# 32_LED.net
KiCad netlist of a schematic drawn in Altium Designer
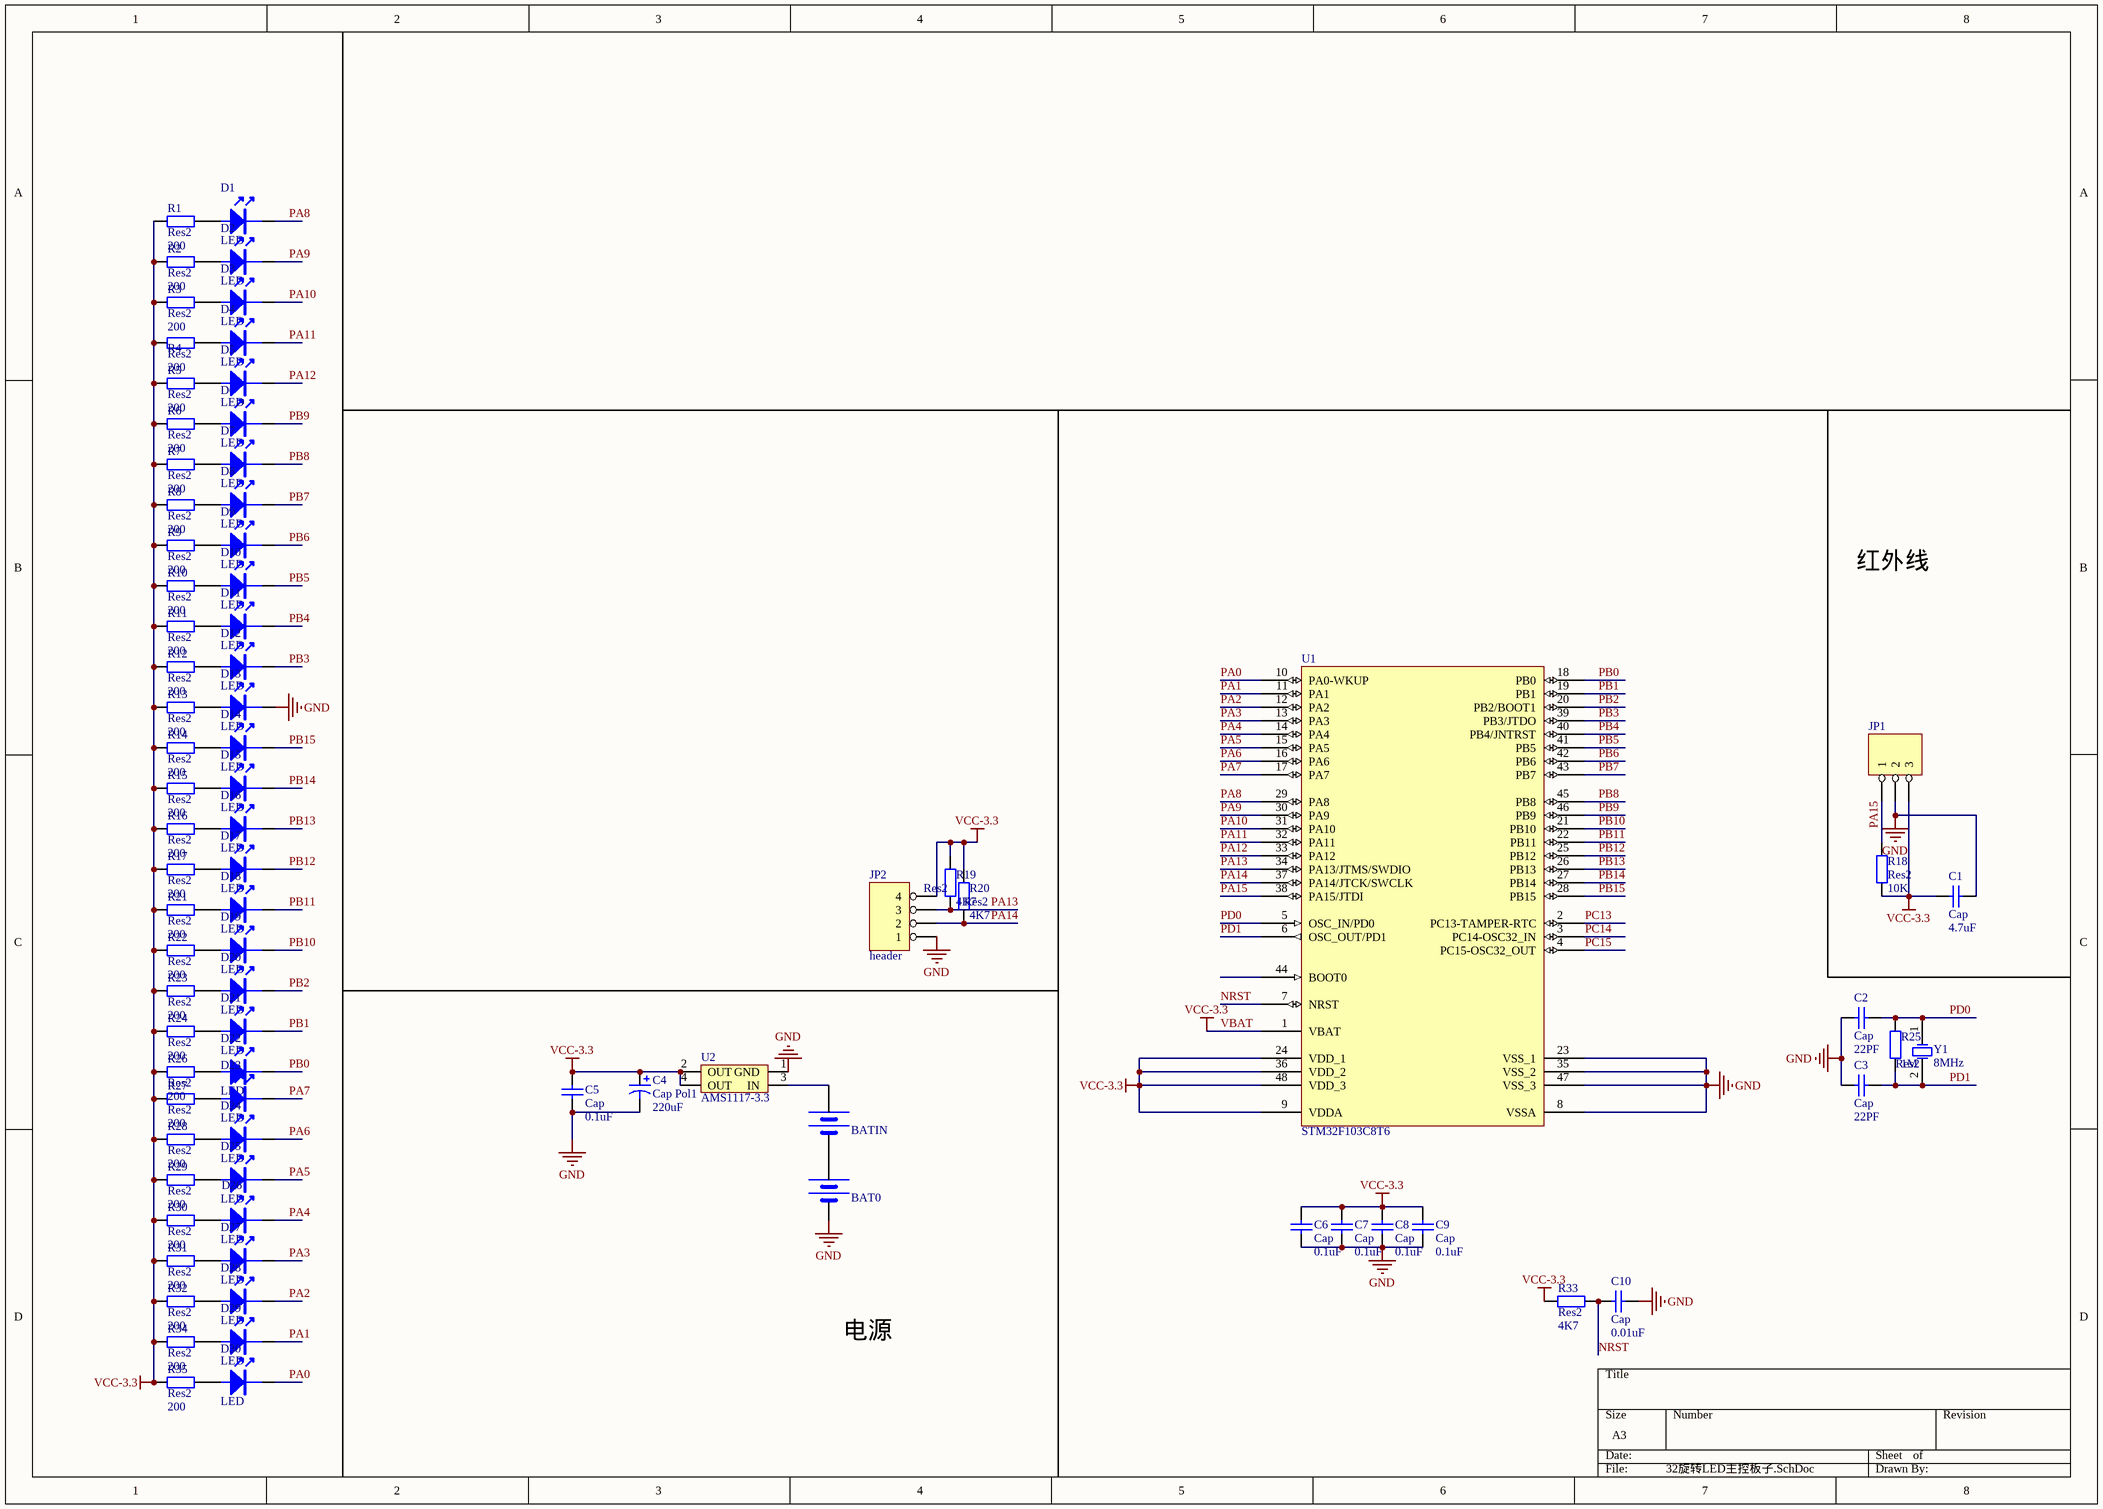
[diagram p0: 32旋转LED主控板子.SchDoc]

(export (version "E")
  (design (tool "Eeschema 10.0.6"))
  (components
    (comp (ref "BAT0")
      (value "BATT")
      (footprint "BATM")
      (libsource (lib "Explorer STM32F407封装库") (part "BAT"))
    )
    (comp (ref "BATIN")
      (value "BATT")
      (footprint "BATM")
      (libsource (lib "Explorer STM32F407封装库") (part "BAT"))
    )
    (comp (ref "C1")
      (value "Cap")
      (footprint "0805_C")
      (description "Capacitor")
      (fields (field (name "ALTIUM_VALUE") "4.7uF") (field (name "PUBLISHER") "Altium Limited"))
      (libsource (lib "Miscellaneous Devices") (part "Cap"))
    )
    (comp (ref "C2")
      (value "Cap")
      (footprint "0805_C")
      (description "Capacitor")
      (fields (field (name "ALTIUM_VALUE") "22PF") (field (name "PUBLISHER") "Altium Limited"))
      (libsource (lib "Miscellaneous Devices") (part "Cap"))
    )
    (comp (ref "C3")
      (value "Cap")
      (footprint "0805_C")
      (description "Capacitor")
      (fields (field (name "ALTIUM_VALUE") "22PF") (field (name "PUBLISHER") "Altium Limited"))
      (libsource (lib "Miscellaneous Devices") (part "Cap"))
    )
    (comp (ref "C4")
      (value "Cap Pol1")
      (footprint "10UF")
      (description "Polarized Capacitor (Radial)")
      (fields (field (name "ALTIUM_VALUE") "220uF") (field (name "PUBLISHER") "Altium Limited"))
      (libsource (lib "Miscellaneous Devices") (part "Cap Pol1"))
    )
    (comp (ref "C5")
      (value "Cap")
      (footprint "0805_C")
      (description "Capacitor")
      (fields (field (name "ALTIUM_VALUE") "0.1uF") (field (name "PUBLISHER") "Altium Limited"))
      (libsource (lib "Miscellaneous Devices") (part "Cap"))
    )
    (comp (ref "C6")
      (value "Cap")
      (footprint "0805_C")
      (description "Capacitor")
      (fields (field (name "ALTIUM_VALUE") "0.1uF") (field (name "PUBLISHER") "Altium Limited"))
      (libsource (lib "Miscellaneous Devices") (part "Cap"))
    )
    (comp (ref "C7")
      (value "Cap")
      (footprint "0805_C")
      (description "Capacitor")
      (fields (field (name "ALTIUM_VALUE") "0.1uF") (field (name "PUBLISHER") "Altium Limited"))
      (libsource (lib "Miscellaneous Devices") (part "Cap"))
    )
    (comp (ref "C8")
      (value "Cap")
      (footprint "0805_C")
      (description "Capacitor")
      (fields (field (name "ALTIUM_VALUE") "0.1uF") (field (name "PUBLISHER") "Altium Limited"))
      (libsource (lib "Miscellaneous Devices") (part "Cap"))
    )
    (comp (ref "C9")
      (value "Cap")
      (footprint "0805_C")
      (description "Capacitor")
      (fields (field (name "ALTIUM_VALUE") "0.1uF") (field (name "PUBLISHER") "Altium Limited"))
      (libsource (lib "Miscellaneous Devices") (part "Cap"))
    )
    (comp (ref "C10")
      (value "Cap")
      (footprint "0805_C")
      (description "Capacitor")
      (fields (field (name "ALTIUM_VALUE") "0.01uF") (field (name "PUBLISHER") "Altium Limited"))
      (libsource (lib "Miscellaneous Devices") (part "Cap"))
    )
    (comp (ref "D1")
      (value "LED")
      (footprint "0805_LED")
      (description "LED 发光二极管")
      (libsource (lib "My Footprint") (part "LED"))
    )
    (comp (ref "D2")
      (value "LED")
      (footprint "0805_LED")
      (description "LED 发光二极管")
      (libsource (lib "My Footprint") (part "LED"))
    )
    (comp (ref "D3")
      (value "LED")
      (footprint "0805_LED")
      (description "LED 发光二极管")
      (libsource (lib "My Footprint") (part "LED"))
    )
    (comp (ref "D4")
      (value "LED")
      (footprint "0805_LED")
      (description "LED 发光二极管")
      (libsource (lib "My Footprint") (part "LED"))
    )
    (comp (ref "D5")
      (value "LED")
      (footprint "0805_LED")
      (description "LED 发光二极管")
      (libsource (lib "My Footprint") (part "LED"))
    )
    (comp (ref "D6")
      (value "LED")
      (footprint "0805_LED")
      (description "LED 发光二极管")
      (libsource (lib "My Footprint") (part "LED"))
    )
    (comp (ref "D7")
      (value "LED")
      (footprint "0805_LED")
      (description "LED 发光二极管")
      (libsource (lib "My Footprint") (part "LED"))
    )
    (comp (ref "D8")
      (value "LED")
      (footprint "0805_LED")
      (description "LED 发光二极管")
      (libsource (lib "My Footprint") (part "LED"))
    )
    (comp (ref "D9")
      (value "LED")
      (footprint "0805_LED")
      (description "LED 发光二极管")
      (libsource (lib "My Footprint") (part "LED"))
    )
    (comp (ref "D10")
      (value "LED")
      (footprint "0805_LED")
      (description "LED 发光二极管")
      (libsource (lib "My Footprint") (part "LED"))
    )
    (comp (ref "D11")
      (value "LED")
      (footprint "0805_LED")
      (description "LED 发光二极管")
      (libsource (lib "My Footprint") (part "LED"))
    )
    (comp (ref "D12")
      (value "LED")
      (footprint "0805_LED")
      (description "LED 发光二极管")
      (libsource (lib "My Footprint") (part "LED"))
    )
    (comp (ref "D13")
      (value "LED")
      (footprint "0805_LED")
      (description "LED 发光二极管")
      (libsource (lib "My Footprint") (part "LED"))
    )
    (comp (ref "D14")
      (value "LED")
      (footprint "0805_LED")
      (description "LED 发光二极管")
      (libsource (lib "My Footprint") (part "LED"))
    )
    (comp (ref "D15")
      (value "LED")
      (footprint "0805_LED")
      (description "LED 发光二极管")
      (libsource (lib "My Footprint") (part "LED"))
    )
    (comp (ref "D16")
      (value "LED")
      (footprint "0805_LED")
      (description "LED 发光二极管")
      (libsource (lib "My Footprint") (part "LED"))
    )
    (comp (ref "D17")
      (value "LED")
      (footprint "0805_LED")
      (description "LED 发光二极管")
      (libsource (lib "My Footprint") (part "LED"))
    )
    (comp (ref "D18")
      (value "LED")
      (footprint "0805_LED")
      (description "LED 发光二极管")
      (libsource (lib "My Footprint") (part "LED"))
    )
    (comp (ref "D19")
      (value "LED")
      (footprint "0805_LED")
      (description "LED 发光二极管")
      (libsource (lib "My Footprint") (part "LED"))
    )
    (comp (ref "D20")
      (value "LED")
      (footprint "0805_LED")
      (description "LED 发光二极管")
      (libsource (lib "My Footprint") (part "LED"))
    )
    (comp (ref "D21")
      (value "LED")
      (footprint "0805_LED")
      (description "LED 发光二极管")
      (libsource (lib "My Footprint") (part "LED"))
    )
    (comp (ref "D22")
      (value "LED")
      (footprint "0805_LED")
      (description "LED 发光二极管")
      (libsource (lib "My Footprint") (part "LED"))
    )
    (comp (ref "D23")
      (value "LED")
      (footprint "0805_LED")
      (description "LED 发光二极管")
      (libsource (lib "My Footprint") (part "LED"))
    )
    (comp (ref "D24")
      (value "LED")
      (footprint "0805_LED")
      (description "LED 发光二极管")
      (libsource (lib "My Footprint") (part "LED"))
    )
    (comp (ref "D25")
      (value "LED")
      (footprint "0805_LED")
      (description "LED 发光二极管")
      (libsource (lib "My Footprint") (part "LED"))
    )
    (comp (ref "D26")
      (value "LED")
      (footprint "0805_LED")
      (description "LED 发光二极管")
      (libsource (lib "My Footprint") (part "LED"))
    )
    (comp (ref "D27")
      (value "LED")
      (footprint "0805_LED")
      (description "LED 发光二极管")
      (libsource (lib "My Footprint") (part "LED"))
    )
    (comp (ref "D28")
      (value "LED")
      (footprint "0805_LED")
      (description "LED 发光二极管")
      (libsource (lib "My Footprint") (part "LED"))
    )
    (comp (ref "D29")
      (value "LED")
      (footprint "0805_LED")
      (description "LED 发光二极管")
      (libsource (lib "My Footprint") (part "LED"))
    )
    (comp (ref "D30")
      (value "LED")
      (footprint "0805_LED")
      (description "LED 发光二极管")
      (libsource (lib "My Footprint") (part "LED"))
    )
    (comp (ref "JP1")
      (value "header")
      (footprint "header3")
      (libsource (lib "My Footprint") (part "HEADER 3"))
    )
    (comp (ref "JP2")
      (value "header")
      (footprint "header4")
      (libsource (lib "My Footprint") (part "HEADER 4"))
    )
    (comp (ref "R1")
      (value "Res2")
      (footprint "0805_R")
      (description "Resistor")
      (fields (field (name "ALTIUM_VALUE") "200") (field (name "PUBLISHER") "Altium Limited"))
      (libsource (lib "Miscellaneous Devices") (part "Res2"))
    )
    (comp (ref "R2")
      (value "Res2")
      (footprint "0805_R")
      (description "Resistor")
      (fields (field (name "ALTIUM_VALUE") "200") (field (name "PUBLISHER") "Altium Limited"))
      (libsource (lib "Miscellaneous Devices") (part "Res2"))
    )
    (comp (ref "R3")
      (value "Res2")
      (footprint "0805_R")
      (description "Resistor")
      (fields (field (name "ALTIUM_VALUE") "200") (field (name "PUBLISHER") "Altium Limited"))
      (libsource (lib "Miscellaneous Devices") (part "Res2"))
    )
    (comp (ref "R4")
      (value "Res2")
      (footprint "0805_R")
      (description "Resistor")
      (fields (field (name "ALTIUM_VALUE") "200") (field (name "PUBLISHER") "Altium Limited"))
      (libsource (lib "Miscellaneous Devices") (part "Res2"))
    )
    (comp (ref "R5")
      (value "Res2")
      (footprint "0805_R")
      (description "Resistor")
      (fields (field (name "ALTIUM_VALUE") "200") (field (name "PUBLISHER") "Altium Limited"))
      (libsource (lib "Miscellaneous Devices") (part "Res2"))
    )
    (comp (ref "R6")
      (value "Res2")
      (footprint "0805_R")
      (description "Resistor")
      (fields (field (name "ALTIUM_VALUE") "200") (field (name "PUBLISHER") "Altium Limited"))
      (libsource (lib "Miscellaneous Devices") (part "Res2"))
    )
    (comp (ref "R7")
      (value "Res2")
      (footprint "0805_R")
      (description "Resistor")
      (fields (field (name "ALTIUM_VALUE") "200") (field (name "PUBLISHER") "Altium Limited"))
      (libsource (lib "Miscellaneous Devices") (part "Res2"))
    )
    (comp (ref "R8")
      (value "Res2")
      (footprint "0805_R")
      (description "Resistor")
      (fields (field (name "ALTIUM_VALUE") "200") (field (name "PUBLISHER") "Altium Limited"))
      (libsource (lib "Miscellaneous Devices") (part "Res2"))
    )
    (comp (ref "R9")
      (value "Res2")
      (footprint "0805_R")
      (description "Resistor")
      (fields (field (name "ALTIUM_VALUE") "200") (field (name "PUBLISHER") "Altium Limited"))
      (libsource (lib "Miscellaneous Devices") (part "Res2"))
    )
    (comp (ref "R10")
      (value "Res2")
      (footprint "0805_R")
      (description "Resistor")
      (fields (field (name "ALTIUM_VALUE") "200") (field (name "PUBLISHER") "Altium Limited"))
      (libsource (lib "Miscellaneous Devices") (part "Res2"))
    )
    (comp (ref "R11")
      (value "Res2")
      (footprint "0805_R")
      (description "Resistor")
      (fields (field (name "ALTIUM_VALUE") "200") (field (name "PUBLISHER") "Altium Limited"))
      (libsource (lib "Miscellaneous Devices") (part "Res2"))
    )
    (comp (ref "R12")
      (value "Res2")
      (footprint "0805_R")
      (description "Resistor")
      (fields (field (name "ALTIUM_VALUE") "200") (field (name "PUBLISHER") "Altium Limited"))
      (libsource (lib "Miscellaneous Devices") (part "Res2"))
    )
    (comp (ref "R13")
      (value "Res2")
      (footprint "0805_R")
      (description "Resistor")
      (fields (field (name "ALTIUM_VALUE") "200") (field (name "PUBLISHER") "Altium Limited"))
      (libsource (lib "Miscellaneous Devices") (part "Res2"))
    )
    (comp (ref "R14")
      (value "Res2")
      (footprint "0805_R")
      (description "Resistor")
      (fields (field (name "ALTIUM_VALUE") "200") (field (name "PUBLISHER") "Altium Limited"))
      (libsource (lib "Miscellaneous Devices") (part "Res2"))
    )
    (comp (ref "R15")
      (value "Res2")
      (footprint "0805_R")
      (description "Resistor")
      (fields (field (name "ALTIUM_VALUE") "200") (field (name "PUBLISHER") "Altium Limited"))
      (libsource (lib "Miscellaneous Devices") (part "Res2"))
    )
    (comp (ref "R16")
      (value "Res2")
      (footprint "0805_R")
      (description "Resistor")
      (fields (field (name "ALTIUM_VALUE") "200") (field (name "PUBLISHER") "Altium Limited"))
      (libsource (lib "Miscellaneous Devices") (part "Res2"))
    )
    (comp (ref "R17")
      (value "Res2")
      (footprint "0805_R")
      (description "Resistor")
      (fields (field (name "ALTIUM_VALUE") "200") (field (name "PUBLISHER") "Altium Limited"))
      (libsource (lib "Miscellaneous Devices") (part "Res2"))
    )
    (comp (ref "R18")
      (value "Res2")
      (footprint "0805_R")
      (description "Resistor")
      (fields (field (name "ALTIUM_VALUE") "10K") (field (name "PUBLISHER") "Altium Limited"))
      (libsource (lib "") (part "Res2_1"))
    )
    (comp (ref "R19")
      (value "Res2")
      (footprint "0805_R")
      (description "Resistor")
      (fields (field (name "ALTIUM_VALUE") "4K7") (field (name "PUBLISHER") "Altium Limited"))
      (libsource (lib "") (part "Res2_1"))
    )
    (comp (ref "R20")
      (value "Res2")
      (footprint "0805_R")
      (description "Resistor")
      (fields (field (name "ALTIUM_VALUE") "4K7") (field (name "PUBLISHER") "Altium Limited"))
      (libsource (lib "") (part "Res2_1"))
    )
    (comp (ref "R21")
      (value "Res2")
      (footprint "0805_R")
      (description "Resistor")
      (fields (field (name "ALTIUM_VALUE") "200") (field (name "PUBLISHER") "Altium Limited"))
      (libsource (lib "Miscellaneous Devices") (part "Res2"))
    )
    (comp (ref "R22")
      (value "Res2")
      (footprint "0805_R")
      (description "Resistor")
      (fields (field (name "ALTIUM_VALUE") "200") (field (name "PUBLISHER") "Altium Limited"))
      (libsource (lib "Miscellaneous Devices") (part "Res2"))
    )
    (comp (ref "R23")
      (value "Res2")
      (footprint "0805_R")
      (description "Resistor")
      (fields (field (name "ALTIUM_VALUE") "200") (field (name "PUBLISHER") "Altium Limited"))
      (libsource (lib "Miscellaneous Devices") (part "Res2"))
    )
    (comp (ref "R24")
      (value "Res2")
      (footprint "0805_R")
      (description "Resistor")
      (fields (field (name "ALTIUM_VALUE") "200") (field (name "PUBLISHER") "Altium Limited"))
      (libsource (lib "Miscellaneous Devices") (part "Res2"))
    )
    (comp (ref "R25")
      (value "Res2")
      (footprint "0805_R")
      (description "Resistor")
      (fields (field (name "ALTIUM_VALUE") "1M") (field (name "PUBLISHER") "Altium Limited"))
      (libsource (lib "") (part "Res2_1"))
    )
    (comp (ref "R26")
      (value "Res2")
      (footprint "0805_R")
      (description "Resistor")
      (fields (field (name "ALTIUM_VALUE") "200") (field (name "PUBLISHER") "Altium Limited"))
      (libsource (lib "Miscellaneous Devices") (part "Res2"))
    )
    (comp (ref "R27")
      (value "Res2")
      (footprint "0805_R")
      (description "Resistor")
      (fields (field (name "ALTIUM_VALUE") "200") (field (name "PUBLISHER") "Altium Limited"))
      (libsource (lib "Miscellaneous Devices") (part "Res2"))
    )
    (comp (ref "R28")
      (value "Res2")
      (footprint "0805_R")
      (description "Resistor")
      (fields (field (name "ALTIUM_VALUE") "200") (field (name "PUBLISHER") "Altium Limited"))
      (libsource (lib "Miscellaneous Devices") (part "Res2"))
    )
    (comp (ref "R29")
      (value "Res2")
      (footprint "0805_R")
      (description "Resistor")
      (fields (field (name "ALTIUM_VALUE") "200") (field (name "PUBLISHER") "Altium Limited"))
      (libsource (lib "Miscellaneous Devices") (part "Res2"))
    )
    (comp (ref "R30")
      (value "Res2")
      (footprint "0805_R")
      (description "Resistor")
      (fields (field (name "ALTIUM_VALUE") "200") (field (name "PUBLISHER") "Altium Limited"))
      (libsource (lib "Miscellaneous Devices") (part "Res2"))
    )
    (comp (ref "R31")
      (value "Res2")
      (footprint "0805_R")
      (description "Resistor")
      (fields (field (name "ALTIUM_VALUE") "200") (field (name "PUBLISHER") "Altium Limited"))
      (libsource (lib "Miscellaneous Devices") (part "Res2"))
    )
    (comp (ref "R32")
      (value "Res2")
      (footprint "0805_R")
      (description "Resistor")
      (fields (field (name "ALTIUM_VALUE") "200") (field (name "PUBLISHER") "Altium Limited"))
      (libsource (lib "Miscellaneous Devices") (part "Res2"))
    )
    (comp (ref "R33")
      (value "Res2")
      (footprint "0805_R")
      (description "Resistor")
      (fields (field (name "ALTIUM_VALUE") "4K7") (field (name "PUBLISHER") "Altium Limited"))
      (libsource (lib "") (part "Res2_2"))
    )
    (comp (ref "R34")
      (value "Res2")
      (footprint "0805_R")
      (description "Resistor")
      (fields (field (name "ALTIUM_VALUE") "200") (field (name "PUBLISHER") "Altium Limited"))
      (libsource (lib "Miscellaneous Devices") (part "Res2"))
    )
    (comp (ref "R35")
      (value "Res2")
      (footprint "0805_R")
      (description "Resistor")
      (fields (field (name "ALTIUM_VALUE") "200") (field (name "PUBLISHER") "Altium Limited"))
      (libsource (lib "Miscellaneous Devices") (part "Res2"))
    )
    (comp (ref "U1")
      (value "STM32F103C8T6")
      (footprint "LQFP48")
      (description "STM32 ARM-based 32-bit MCU with 64 Kbytes Flash, 48-pin LQFP, Industrial Temperature")
      (fields (field (name "PUBLISHER") "Altium Limited"))
      (libsource (lib "My Footprint") (part "STM32F103C8T6"))
    )
    (comp (ref "U2")
      (value "AMS1117-3.3")
      (footprint "AMS1117")
      (libsource (lib "Explorer STM32F407封装库") (part "AMS1117"))
    )
    (comp (ref "Y1")
      (value "8MHz")
      (footprint "XTAL_2")
      (description "Crystal Oscillator")
      (fields (field (name "PUBLISHER") "Altium Limited"))
      (libsource (lib "Explorer STM32F407封装库") (part "XTAL"))
    )
  )
  (nets
    (net (code "1") (name "/NRST") (class "Default")
      (node (ref "C10") (pin "1") (pinfunction "1_1") (pintype "passive"))
      (node (ref "R33") (pin "2") (pinfunction "2_2") (pintype "passive"))
      (node (ref "U1") (pin "7") (pinfunction "NRST_7") (pintype "bidirectional"))
    )
    (net (code "2") (name "/PA0") (class "Default")
      (node (ref "D30") (pin "2") (pinfunction "K_2") (pintype "passive"))
      (node (ref "U1") (pin "10") (pinfunction "PA0-WKUP_10") (pintype "bidirectional"))
    )
    (net (code "3") (name "/PA1") (class "Default")
      (node (ref "D29") (pin "2") (pinfunction "K_2") (pintype "passive"))
      (node (ref "U1") (pin "11") (pinfunction "PA1_11") (pintype "bidirectional"))
    )
    (net (code "4") (name "/PA2") (class "Default")
      (node (ref "D28") (pin "2") (pinfunction "K_2") (pintype "passive"))
      (node (ref "U1") (pin "12") (pinfunction "PA2_12") (pintype "bidirectional"))
    )
    (net (code "5") (name "/PA3") (class "Default")
      (node (ref "D27") (pin "2") (pinfunction "K_2") (pintype "passive"))
      (node (ref "U1") (pin "13") (pinfunction "PA3_13") (pintype "bidirectional"))
    )
    (net (code "6") (name "/PA4") (class "Default")
      (node (ref "D26") (pin "2") (pinfunction "K_2") (pintype "passive"))
      (node (ref "U1") (pin "14") (pinfunction "PA4_14") (pintype "bidirectional"))
    )
    (net (code "7") (name "/PA5") (class "Default")
      (node (ref "D25") (pin "2") (pinfunction "K_2") (pintype "passive"))
      (node (ref "U1") (pin "15") (pinfunction "PA5_15") (pintype "bidirectional"))
    )
    (net (code "8") (name "/PA6") (class "Default")
      (node (ref "D24") (pin "2") (pinfunction "K_2") (pintype "passive"))
      (node (ref "U1") (pin "16") (pinfunction "PA6_16") (pintype "bidirectional"))
    )
    (net (code "9") (name "/PA7") (class "Default")
      (node (ref "D23") (pin "2") (pinfunction "K_2") (pintype "passive"))
      (node (ref "U1") (pin "17") (pinfunction "PA7_17") (pintype "bidirectional"))
    )
    (net (code "10") (name "/PA8") (class "Default")
      (node (ref "D1") (pin "2") (pinfunction "K_2") (pintype "passive"))
      (node (ref "U1") (pin "29") (pinfunction "PA8_29") (pintype "bidirectional"))
    )
    (net (code "11") (name "/PA9") (class "Default")
      (node (ref "D2") (pin "2") (pinfunction "K_2") (pintype "passive"))
      (node (ref "U1") (pin "30") (pinfunction "PA9_30") (pintype "bidirectional"))
    )
    (net (code "12") (name "/PA10") (class "Default")
      (node (ref "D3") (pin "2") (pinfunction "K_2") (pintype "passive"))
      (node (ref "U1") (pin "31") (pinfunction "PA10_31") (pintype "bidirectional"))
    )
    (net (code "13") (name "/PA11") (class "Default")
      (node (ref "D4") (pin "2") (pinfunction "K_2") (pintype "passive"))
      (node (ref "U1") (pin "32") (pinfunction "PA11_32") (pintype "bidirectional"))
    )
    (net (code "14") (name "/PA12") (class "Default")
      (node (ref "D5") (pin "2") (pinfunction "K_2") (pintype "passive"))
      (node (ref "U1") (pin "33") (pinfunction "PA12_33") (pintype "bidirectional"))
    )
    (net (code "15") (name "/PA13") (class "Default")
      (node (ref "JP2") (pin "3") (pinfunction "3_3") (pintype "passive"))
      (node (ref "R19") (pin "1") (pinfunction "1_1") (pintype "passive"))
      (node (ref "U1") (pin "34") (pinfunction "PA13/JTMS/SWDIO_34") (pintype "bidirectional"))
    )
    (net (code "16") (name "/PA14") (class "Default")
      (node (ref "JP2") (pin "2") (pinfunction "2_2") (pintype "passive"))
      (node (ref "R20") (pin "1") (pinfunction "1_1") (pintype "passive"))
      (node (ref "U1") (pin "37") (pinfunction "PA14/JTCK/SWCLK_37") (pintype "bidirectional"))
    )
    (net (code "17") (name "/PA15") (class "Default")
      (node (ref "JP1") (pin "1") (pinfunction "1_1") (pintype "passive"))
      (node (ref "R18") (pin "2") (pinfunction "2_2") (pintype "passive"))
      (node (ref "U1") (pin "38") (pinfunction "PA15/JTDI_38") (pintype "bidirectional"))
    )
    (net (code "18") (name "/PB0") (class "Default")
      (node (ref "D22") (pin "2") (pinfunction "K_2") (pintype "passive"))
      (node (ref "U1") (pin "18") (pinfunction "PB0_18") (pintype "bidirectional"))
    )
    (net (code "19") (name "/PB1") (class "Default")
      (node (ref "D21") (pin "2") (pinfunction "K_2") (pintype "passive"))
      (node (ref "U1") (pin "19") (pinfunction "PB1_19") (pintype "bidirectional"))
    )
    (net (code "20") (name "/PB2") (class "Default")
      (node (ref "D20") (pin "2") (pinfunction "K_2") (pintype "passive"))
      (node (ref "U1") (pin "20") (pinfunction "PB2/BOOT1_20") (pintype "bidirectional"))
    )
    (net (code "21") (name "/PB3") (class "Default")
      (node (ref "D12") (pin "2") (pinfunction "K_2") (pintype "passive"))
      (node (ref "U1") (pin "39") (pinfunction "PB3/JTDO_39") (pintype "bidirectional"))
    )
    (net (code "22") (name "/PB4") (class "Default")
      (node (ref "D11") (pin "2") (pinfunction "K_2") (pintype "passive"))
      (node (ref "U1") (pin "40") (pinfunction "PB4/JNTRST_40") (pintype "bidirectional"))
    )
    (net (code "23") (name "/PB5") (class "Default")
      (node (ref "D10") (pin "2") (pinfunction "K_2") (pintype "passive"))
      (node (ref "U1") (pin "41") (pinfunction "PB5_41") (pintype "bidirectional"))
    )
    (net (code "24") (name "/PB6") (class "Default")
      (node (ref "D9") (pin "2") (pinfunction "K_2") (pintype "passive"))
      (node (ref "U1") (pin "42") (pinfunction "PB6_42") (pintype "bidirectional"))
    )
    (net (code "25") (name "/PB7") (class "Default")
      (node (ref "D8") (pin "2") (pinfunction "K_2") (pintype "passive"))
      (node (ref "U1") (pin "43") (pinfunction "PB7_43") (pintype "bidirectional"))
    )
    (net (code "26") (name "/PB8") (class "Default")
      (node (ref "D7") (pin "2") (pinfunction "K_2") (pintype "passive"))
      (node (ref "U1") (pin "45") (pinfunction "PB8_45") (pintype "bidirectional"))
    )
    (net (code "27") (name "/PB9") (class "Default")
      (node (ref "D6") (pin "2") (pinfunction "K_2") (pintype "passive"))
      (node (ref "U1") (pin "46") (pinfunction "PB9_46") (pintype "bidirectional"))
    )
    (net (code "28") (name "/PB10") (class "Default")
      (node (ref "D19") (pin "2") (pinfunction "K_2") (pintype "passive"))
      (node (ref "U1") (pin "21") (pinfunction "PB10_21") (pintype "bidirectional"))
    )
    (net (code "29") (name "/PB11") (class "Default")
      (node (ref "D18") (pin "2") (pinfunction "K_2") (pintype "passive"))
      (node (ref "U1") (pin "22") (pinfunction "PB11_22") (pintype "bidirectional"))
    )
    (net (code "30") (name "/PB12") (class "Default")
      (node (ref "D17") (pin "2") (pinfunction "K_2") (pintype "passive"))
      (node (ref "U1") (pin "25") (pinfunction "PB12_25") (pintype "bidirectional"))
    )
    (net (code "31") (name "/PB13") (class "Default")
      (node (ref "D16") (pin "2") (pinfunction "K_2") (pintype "passive"))
      (node (ref "U1") (pin "26") (pinfunction "PB13_26") (pintype "bidirectional"))
    )
    (net (code "32") (name "/PB14") (class "Default")
      (node (ref "D15") (pin "2") (pinfunction "K_2") (pintype "passive"))
      (node (ref "U1") (pin "27") (pinfunction "PB14_27") (pintype "bidirectional"))
    )
    (net (code "33") (name "/PB15") (class "Default")
      (node (ref "D14") (pin "2") (pinfunction "K_2") (pintype "passive"))
      (node (ref "U1") (pin "28") (pinfunction "PB15_28") (pintype "bidirectional"))
    )
    (net (code "34") (name "/PC13") (class "Default")
      (node (ref "U1") (pin "2") (pinfunction "PC13-TAMPER-RTC_2") (pintype "bidirectional"))
    )
    (net (code "35") (name "/PC14") (class "Default")
      (node (ref "U1") (pin "3") (pinfunction "PC14-OSC32_IN_3") (pintype "bidirectional"))
    )
    (net (code "36") (name "/PC15") (class "Default")
      (node (ref "U1") (pin "4") (pinfunction "PC15-OSC32_OUT_4") (pintype "bidirectional"))
    )
    (net (code "37") (name "/PD0") (class "Default")
      (node (ref "C2") (pin "2") (pinfunction "2_2") (pintype "passive"))
      (node (ref "R25") (pin "2") (pinfunction "2_2") (pintype "passive"))
      (node (ref "U1") (pin "5") (pinfunction "OSC_IN/PD0_5") (pintype "input"))
      (node (ref "Y1") (pin "1") (pinfunction "OSC1_1") (pintype "passive"))
    )
    (net (code "38") (name "/PD1") (class "Default")
      (node (ref "C3") (pin "2") (pinfunction "2_2") (pintype "passive"))
      (node (ref "R25") (pin "1") (pinfunction "1_1") (pintype "passive"))
      (node (ref "U1") (pin "6") (pinfunction "OSC_OUT/PD1_6") (pintype "output"))
      (node (ref "Y1") (pin "2") (pinfunction "OSC2_2") (pintype "passive"))
    )
    (net (code "39") (name "GND") (class "Default")
      (node (ref "BAT0") (pin "2") (pinfunction "GND_2") (pintype "passive"))
      (node (ref "C1") (pin "2") (pinfunction "2_2") (pintype "passive"))
      (node (ref "C10") (pin "2") (pinfunction "2_2") (pintype "passive"))
      (node (ref "C2") (pin "1") (pinfunction "1_1") (pintype "passive"))
      (node (ref "C3") (pin "1") (pinfunction "1_1") (pintype "passive"))
      (node (ref "C4") (pin "2") (pinfunction "2_2") (pintype "passive"))
      (node (ref "C5") (pin "1") (pinfunction "1_1") (pintype "passive"))
      (node (ref "C6") (pin "1") (pinfunction "1_1") (pintype "passive"))
      (node (ref "C7") (pin "1") (pinfunction "1_1") (pintype "passive"))
      (node (ref "C8") (pin "1") (pinfunction "1_1") (pintype "passive"))
      (node (ref "C9") (pin "1") (pinfunction "1_1") (pintype "passive"))
      (node (ref "D13") (pin "2") (pinfunction "K_2") (pintype "passive"))
      (node (ref "JP1") (pin "2") (pinfunction "2_2") (pintype "passive"))
      (node (ref "JP2") (pin "1") (pinfunction "1_1") (pintype "passive"))
      (node (ref "U1") (pin "23") (pinfunction "VSS_1_23") (pintype "power_in"))
      (node (ref "U1") (pin "35") (pinfunction "VSS_2_35") (pintype "power_in"))
      (node (ref "U1") (pin "47") (pinfunction "VSS_3_47") (pintype "power_in"))
      (node (ref "U1") (pin "8") (pinfunction "VSSA_8") (pintype "power_in"))
      (node (ref "U2") (pin "1") (pinfunction "GND_1") (pintype "passive"))
    )
    (net (code "40") (name "Net-(BAT0-VCC)") (class "Default")
      (node (ref "BAT0") (pin "1") (pinfunction "VCC_1") (pintype "passive"))
      (node (ref "BATIN") (pin "2") (pinfunction "GND_2") (pintype "passive"))
    )
    (net (code "41") (name "Net-(BATIN-VCC)") (class "Default")
      (node (ref "BATIN") (pin "1") (pinfunction "VCC_1") (pintype "passive"))
      (node (ref "U2") (pin "3") (pinfunction "IN_3") (pintype "passive"))
    )
    (net (code "42") (name "Net-(D1-A)") (class "Default")
      (node (ref "D1") (pin "1") (pinfunction "A_1") (pintype "passive"))
      (node (ref "R1") (pin "1") (pinfunction "1_1") (pintype "passive"))
    )
    (net (code "43") (name "Net-(D2-A)") (class "Default")
      (node (ref "D2") (pin "1") (pinfunction "A_1") (pintype "passive"))
      (node (ref "R2") (pin "1") (pinfunction "1_1") (pintype "passive"))
    )
    (net (code "44") (name "Net-(D3-A)") (class "Default")
      (node (ref "D3") (pin "1") (pinfunction "A_1") (pintype "passive"))
      (node (ref "R3") (pin "1") (pinfunction "1_1") (pintype "passive"))
    )
    (net (code "45") (name "Net-(D4-A)") (class "Default")
      (node (ref "D4") (pin "1") (pinfunction "A_1") (pintype "passive"))
      (node (ref "R4") (pin "1") (pinfunction "1_1") (pintype "passive"))
    )
    (net (code "46") (name "Net-(D5-A)") (class "Default")
      (node (ref "D5") (pin "1") (pinfunction "A_1") (pintype "passive"))
      (node (ref "R5") (pin "1") (pinfunction "1_1") (pintype "passive"))
    )
    (net (code "47") (name "Net-(D6-A)") (class "Default")
      (node (ref "D6") (pin "1") (pinfunction "A_1") (pintype "passive"))
      (node (ref "R6") (pin "1") (pinfunction "1_1") (pintype "passive"))
    )
    (net (code "48") (name "Net-(D7-A)") (class "Default")
      (node (ref "D7") (pin "1") (pinfunction "A_1") (pintype "passive"))
      (node (ref "R7") (pin "1") (pinfunction "1_1") (pintype "passive"))
    )
    (net (code "49") (name "Net-(D8-A)") (class "Default")
      (node (ref "D8") (pin "1") (pinfunction "A_1") (pintype "passive"))
      (node (ref "R8") (pin "1") (pinfunction "1_1") (pintype "passive"))
    )
    (net (code "50") (name "Net-(D9-A)") (class "Default")
      (node (ref "D9") (pin "1") (pinfunction "A_1") (pintype "passive"))
      (node (ref "R9") (pin "1") (pinfunction "1_1") (pintype "passive"))
    )
    (net (code "51") (name "Net-(D10-A)") (class "Default")
      (node (ref "D10") (pin "1") (pinfunction "A_1") (pintype "passive"))
      (node (ref "R10") (pin "1") (pinfunction "1_1") (pintype "passive"))
    )
    (net (code "52") (name "Net-(D11-A)") (class "Default")
      (node (ref "D11") (pin "1") (pinfunction "A_1") (pintype "passive"))
      (node (ref "R11") (pin "1") (pinfunction "1_1") (pintype "passive"))
    )
    (net (code "53") (name "Net-(D12-A)") (class "Default")
      (node (ref "D12") (pin "1") (pinfunction "A_1") (pintype "passive"))
      (node (ref "R12") (pin "1") (pinfunction "1_1") (pintype "passive"))
    )
    (net (code "54") (name "Net-(D13-A)") (class "Default")
      (node (ref "D13") (pin "1") (pinfunction "A_1") (pintype "passive"))
      (node (ref "R13") (pin "1") (pinfunction "1_1") (pintype "passive"))
    )
    (net (code "55") (name "Net-(D14-A)") (class "Default")
      (node (ref "D14") (pin "1") (pinfunction "A_1") (pintype "passive"))
      (node (ref "R14") (pin "1") (pinfunction "1_1") (pintype "passive"))
    )
    (net (code "56") (name "Net-(D15-A)") (class "Default")
      (node (ref "D15") (pin "1") (pinfunction "A_1") (pintype "passive"))
      (node (ref "R15") (pin "1") (pinfunction "1_1") (pintype "passive"))
    )
    (net (code "57") (name "Net-(D16-A)") (class "Default")
      (node (ref "D16") (pin "1") (pinfunction "A_1") (pintype "passive"))
      (node (ref "R16") (pin "1") (pinfunction "1_1") (pintype "passive"))
    )
    (net (code "58") (name "Net-(D17-A)") (class "Default")
      (node (ref "D17") (pin "1") (pinfunction "A_1") (pintype "passive"))
      (node (ref "R17") (pin "1") (pinfunction "1_1") (pintype "passive"))
    )
    (net (code "59") (name "Net-(D18-A)") (class "Default")
      (node (ref "D18") (pin "1") (pinfunction "A_1") (pintype "passive"))
      (node (ref "R21") (pin "1") (pinfunction "1_1") (pintype "passive"))
    )
    (net (code "60") (name "Net-(D19-A)") (class "Default")
      (node (ref "D19") (pin "1") (pinfunction "A_1") (pintype "passive"))
      (node (ref "R22") (pin "1") (pinfunction "1_1") (pintype "passive"))
    )
    (net (code "61") (name "Net-(D20-A)") (class "Default")
      (node (ref "D20") (pin "1") (pinfunction "A_1") (pintype "passive"))
      (node (ref "R23") (pin "1") (pinfunction "1_1") (pintype "passive"))
    )
    (net (code "62") (name "Net-(D21-A)") (class "Default")
      (node (ref "D21") (pin "1") (pinfunction "A_1") (pintype "passive"))
      (node (ref "R24") (pin "1") (pinfunction "1_1") (pintype "passive"))
    )
    (net (code "63") (name "Net-(D22-A)") (class "Default")
      (node (ref "D22") (pin "1") (pinfunction "A_1") (pintype "passive"))
      (node (ref "R26") (pin "1") (pinfunction "1_1") (pintype "passive"))
    )
    (net (code "64") (name "Net-(D23-A)") (class "Default")
      (node (ref "D23") (pin "1") (pinfunction "A_1") (pintype "passive"))
      (node (ref "R27") (pin "1") (pinfunction "1_1") (pintype "passive"))
    )
    (net (code "65") (name "Net-(D24-A)") (class "Default")
      (node (ref "D24") (pin "1") (pinfunction "A_1") (pintype "passive"))
      (node (ref "R28") (pin "1") (pinfunction "1_1") (pintype "passive"))
    )
    (net (code "66") (name "Net-(D25-A)") (class "Default")
      (node (ref "D25") (pin "1") (pinfunction "A_1") (pintype "passive"))
      (node (ref "R29") (pin "1") (pinfunction "1_1") (pintype "passive"))
    )
    (net (code "67") (name "Net-(D26-A)") (class "Default")
      (node (ref "D26") (pin "1") (pinfunction "A_1") (pintype "passive"))
      (node (ref "R30") (pin "1") (pinfunction "1_1") (pintype "passive"))
    )
    (net (code "68") (name "Net-(D27-A)") (class "Default")
      (node (ref "D27") (pin "1") (pinfunction "A_1") (pintype "passive"))
      (node (ref "R31") (pin "1") (pinfunction "1_1") (pintype "passive"))
    )
    (net (code "69") (name "Net-(D28-A)") (class "Default")
      (node (ref "D28") (pin "1") (pinfunction "A_1") (pintype "passive"))
      (node (ref "R32") (pin "1") (pinfunction "1_1") (pintype "passive"))
    )
    (net (code "70") (name "Net-(D29-A)") (class "Default")
      (node (ref "D29") (pin "1") (pinfunction "A_1") (pintype "passive"))
      (node (ref "R34") (pin "1") (pinfunction "1_1") (pintype "passive"))
    )
    (net (code "71") (name "Net-(D30-A)") (class "Default")
      (node (ref "D30") (pin "1") (pinfunction "A_1") (pintype "passive"))
      (node (ref "R35") (pin "1") (pinfunction "1_1") (pintype "passive"))
    )
    (net (code "72") (name "VCC-3.3") (class "Default")
      (node (ref "C1") (pin "1") (pinfunction "1_1") (pintype "passive"))
      (node (ref "C4") (pin "1") (pinfunction "1_1") (pintype "passive"))
      (node (ref "C5") (pin "2") (pinfunction "2_2") (pintype "passive"))
      (node (ref "C6") (pin "2") (pinfunction "2_2") (pintype "passive"))
      (node (ref "C7") (pin "2") (pinfunction "2_2") (pintype "passive"))
      (node (ref "C8") (pin "2") (pinfunction "2_2") (pintype "passive"))
      (node (ref "C9") (pin "2") (pinfunction "2_2") (pintype "passive"))
      (node (ref "JP1") (pin "3") (pinfunction "3_3") (pintype "passive"))
      (node (ref "JP2") (pin "4") (pinfunction "4_4") (pintype "passive"))
      (node (ref "R1") (pin "2") (pinfunction "2_2") (pintype "passive"))
      (node (ref "R10") (pin "2") (pinfunction "2_2") (pintype "passive"))
      (node (ref "R11") (pin "2") (pinfunction "2_2") (pintype "passive"))
      (node (ref "R12") (pin "2") (pinfunction "2_2") (pintype "passive"))
      (node (ref "R13") (pin "2") (pinfunction "2_2") (pintype "passive"))
      (node (ref "R14") (pin "2") (pinfunction "2_2") (pintype "passive"))
      (node (ref "R15") (pin "2") (pinfunction "2_2") (pintype "passive"))
      (node (ref "R16") (pin "2") (pinfunction "2_2") (pintype "passive"))
      (node (ref "R17") (pin "2") (pinfunction "2_2") (pintype "passive"))
      (node (ref "R18") (pin "1") (pinfunction "1_1") (pintype "passive"))
      (node (ref "R19") (pin "2") (pinfunction "2_2") (pintype "passive"))
      (node (ref "R2") (pin "2") (pinfunction "2_2") (pintype "passive"))
      (node (ref "R20") (pin "2") (pinfunction "2_2") (pintype "passive"))
      (node (ref "R21") (pin "2") (pinfunction "2_2") (pintype "passive"))
      (node (ref "R22") (pin "2") (pinfunction "2_2") (pintype "passive"))
      (node (ref "R23") (pin "2") (pinfunction "2_2") (pintype "passive"))
      (node (ref "R24") (pin "2") (pinfunction "2_2") (pintype "passive"))
      (node (ref "R26") (pin "2") (pinfunction "2_2") (pintype "passive"))
      (node (ref "R27") (pin "2") (pinfunction "2_2") (pintype "passive"))
      (node (ref "R28") (pin "2") (pinfunction "2_2") (pintype "passive"))
      (node (ref "R29") (pin "2") (pinfunction "2_2") (pintype "passive"))
      (node (ref "R3") (pin "2") (pinfunction "2_2") (pintype "passive"))
      (node (ref "R30") (pin "2") (pinfunction "2_2") (pintype "passive"))
      (node (ref "R31") (pin "2") (pinfunction "2_2") (pintype "passive"))
      (node (ref "R32") (pin "2") (pinfunction "2_2") (pintype "passive"))
      (node (ref "R33") (pin "1") (pinfunction "1_1") (pintype "passive"))
      (node (ref "R34") (pin "2") (pinfunction "2_2") (pintype "passive"))
      (node (ref "R35") (pin "2") (pinfunction "2_2") (pintype "passive"))
      (node (ref "R4") (pin "2") (pinfunction "2_2") (pintype "passive"))
      (node (ref "R5") (pin "2") (pinfunction "2_2") (pintype "passive"))
      (node (ref "R6") (pin "2") (pinfunction "2_2") (pintype "passive"))
      (node (ref "R7") (pin "2") (pinfunction "2_2") (pintype "passive"))
      (node (ref "R8") (pin "2") (pinfunction "2_2") (pintype "passive"))
      (node (ref "R9") (pin "2") (pinfunction "2_2") (pintype "passive"))
      (node (ref "U1") (pin "1") (pinfunction "VBAT_1") (pintype "power_in"))
      (node (ref "U1") (pin "24") (pinfunction "VDD_1_24") (pintype "power_in"))
      (node (ref "U1") (pin "36") (pinfunction "VDD_2_36") (pintype "power_in"))
      (node (ref "U1") (pin "48") (pinfunction "VDD_3_48") (pintype "power_in"))
      (node (ref "U1") (pin "9") (pinfunction "VDDA_9") (pintype "power_in"))
      (node (ref "U2") (pin "2") (pinfunction "OUT_2") (pintype "passive"))
      (node (ref "U2") (pin "4") (pinfunction "OUT_4") (pintype "passive"))
    )
    (net (code "73") (name "unconnected-(U1-BOOT0-Pad44)") (class "Default")
      (node (ref "U1") (pin "44") (pinfunction "BOOT0_44") (pintype "input"))
    )
  )
)
